# Audio.net
KiCad netlist of a schematic drawn in Altium Designer
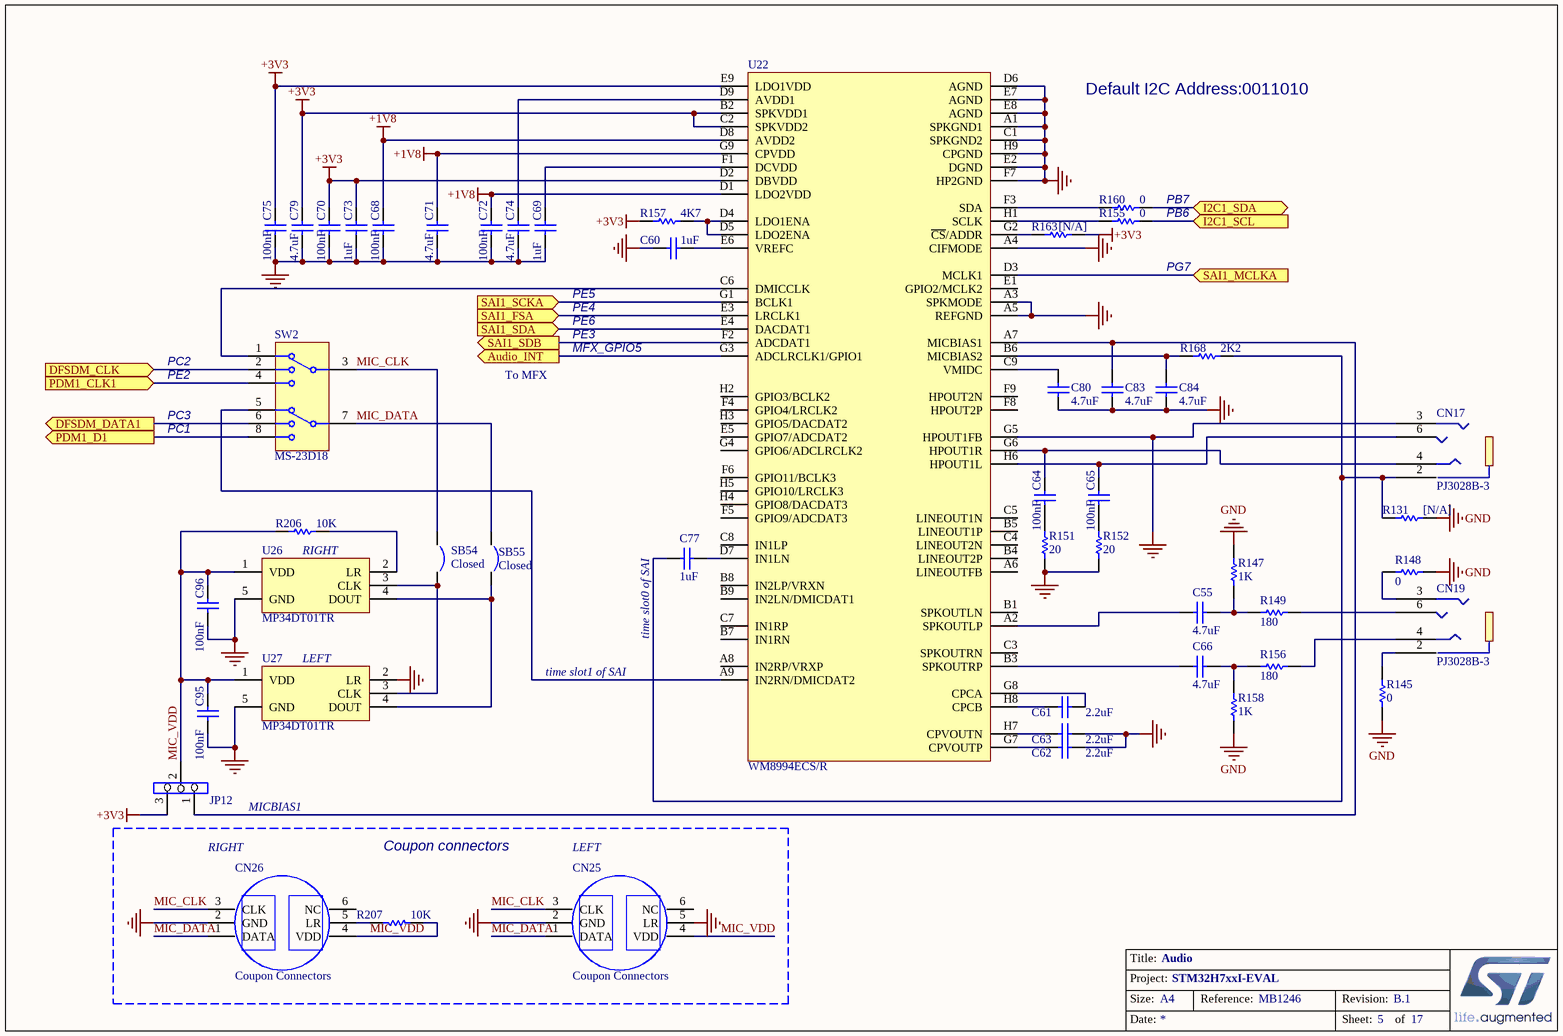
[diagram p0: Audio.SchDoc]

(export (version "E")
  (design (tool "Eeschema 10.0.6"))
  (components
    (comp (ref "C55")
      (value "4.7uF")
      (footprint "0603C")
      (description "Capacitor")
      (fields (field (name "PUBLISHER") "Altium Limited"))
      (libsource (lib "Miscellaneous Devices") (part "Cap"))
    )
    (comp (ref "C60")
      (value "1uF")
      (footprint "0603C")
      (description "Capacitor")
      (fields (field (name "PUBLISHER") "Altium Limited"))
      (libsource (lib "Miscellaneous Devices") (part "CAP"))
    )
    (comp (ref "C61")
      (value "2.2uF")
      (footprint "0603C")
      (description "Capacitor")
      (fields (field (name "PUBLISHER") "Altium Limited"))
      (libsource (lib "Miscellaneous Devices") (part "CAP"))
    )
    (comp (ref "C62")
      (value "2.2uF")
      (footprint "0603C")
      (description "Capacitor")
      (fields (field (name "PUBLISHER") "Altium Limited"))
      (libsource (lib "Miscellaneous Devices") (part "CAP"))
    )
    (comp (ref "C63")
      (value "2.2uF")
      (footprint "0603C")
      (description "Capacitor")
      (fields (field (name "PUBLISHER") "Altium Limited"))
      (libsource (lib "Miscellaneous Devices") (part "CAP"))
    )
    (comp (ref "C64")
      (value "100nF")
      (footprint "0603C")
      (description "Capacitor")
      (fields (field (name "PUBLISHER") "Altium Limited"))
      (libsource (lib "Miscellaneous Devices") (part "Cap"))
    )
    (comp (ref "C65")
      (value "100nF")
      (footprint "0603C")
      (description "Capacitor")
      (fields (field (name "PUBLISHER") "Altium Limited"))
      (libsource (lib "Miscellaneous Devices") (part "Cap"))
    )
    (comp (ref "C66")
      (value "4.7uF")
      (footprint "0603C")
      (description "Capacitor")
      (fields (field (name "PUBLISHER") "Altium Limited"))
      (libsource (lib "Miscellaneous Devices") (part "Cap"))
    )
    (comp (ref "C68")
      (value "100nF")
      (footprint "0603C")
      (description "Capacitor")
      (fields (field (name "PUBLISHER") "Altium Limited"))
      (libsource (lib "Miscellaneous Devices") (part "Cap"))
    )
    (comp (ref "C69")
      (value "1uF")
      (footprint "0603C")
      (description "Capacitor")
      (fields (field (name "PUBLISHER") "Altium Limited"))
      (libsource (lib "Miscellaneous Devices") (part "CAP"))
    )
    (comp (ref "C70")
      (value "100nF")
      (footprint "0603C")
      (description "Capacitor")
      (fields (field (name "PUBLISHER") "Altium Limited"))
      (libsource (lib "Miscellaneous Devices") (part "Cap"))
    )
    (comp (ref "C71")
      (value "4.7uF")
      (footprint "0603C")
      (description "Capacitor")
      (fields (field (name "PUBLISHER") "Altium Limited"))
      (libsource (lib "Miscellaneous Devices") (part "Cap"))
    )
    (comp (ref "C72")
      (value "100nF")
      (footprint "0603C")
      (description "Capacitor")
      (fields (field (name "PUBLISHER") "Altium Limited"))
      (libsource (lib "Miscellaneous Devices") (part "Cap"))
    )
    (comp (ref "C73")
      (value "1uF")
      (footprint "0603C")
      (description "Capacitor")
      (fields (field (name "PUBLISHER") "Altium Limited"))
      (libsource (lib "Miscellaneous Devices") (part "CAP"))
    )
    (comp (ref "C74")
      (value "4.7uF")
      (footprint "0603C")
      (description "Capacitor")
      (fields (field (name "PUBLISHER") "Altium Limited"))
      (libsource (lib "Miscellaneous Devices") (part "Cap"))
    )
    (comp (ref "C75")
      (value "100nF")
      (footprint "0603C")
      (description "Capacitor")
      (fields (field (name "PUBLISHER") "Altium Limited"))
      (libsource (lib "Miscellaneous Devices") (part "Cap"))
    )
    (comp (ref "C77")
      (value "1uF")
      (footprint "0603C")
      (description "Capacitor")
      (fields (field (name "PUBLISHER") "Altium Limited"))
      (libsource (lib "Miscellaneous Devices") (part "CAP"))
    )
    (comp (ref "C79")
      (value "4.7uF")
      (footprint "0603C")
      (description "Capacitor")
      (fields (field (name "PUBLISHER") "Altium Limited"))
      (libsource (lib "Miscellaneous Devices") (part "Cap"))
    )
    (comp (ref "C80")
      (value "4.7uF")
      (footprint "0603C")
      (description "Capacitor")
      (fields (field (name "PUBLISHER") "Altium Limited"))
      (libsource (lib "Miscellaneous Devices") (part "Cap"))
    )
    (comp (ref "C83")
      (value "4.7uF")
      (footprint "0603C")
      (description "Capacitor")
      (fields (field (name "PUBLISHER") "Altium Limited"))
      (libsource (lib "Miscellaneous Devices") (part "Cap"))
    )
    (comp (ref "C84")
      (value "4.7uF")
      (footprint "0603C")
      (description "Capacitor")
      (fields (field (name "PUBLISHER") "Altium Limited"))
      (libsource (lib "Miscellaneous Devices") (part "Cap"))
    )
    (comp (ref "C95")
      (value "100nF")
      (footprint "0603C")
      (description "Capacitor")
      (fields (field (name "PUBLISHER") "Altium Limited"))
      (libsource (lib "Miscellaneous Devices") (part "Cap"))
    )
    (comp (ref "C96")
      (value "100nF")
      (footprint "0603C")
      (description "Capacitor")
      (fields (field (name "PUBLISHER") "Altium Limited"))
      (libsource (lib "Miscellaneous Devices") (part "Cap"))
    )
    (comp (ref "CN17") (value "PJ3028B-3") (footprint "PJ3028B") (libsource (lib "MB786") (part "PJ3028B-3")))
    (comp (ref "CN19") (value "PJ3028B-3") (footprint "PJ3028B") (libsource (lib "MB786") (part "PJ3028B-3")))
    (comp (ref "CN25")
      (value "Coupon Connectors")
      (footprint "Coupon")
      (description "Header, 3-Pin, Single row")
      (fields (field (name "PUBLISHER") "Altium Limited"))
      (libsource (lib "MB1167") (part "Coupon Connectors"))
    )
    (comp (ref "CN26")
      (value "Coupon Connectors")
      (footprint "Coupon")
      (description "Header, 3-Pin, Single row")
      (fields (field (name "PUBLISHER") "Altium Limited"))
      (libsource (lib "MB1167") (part "Coupon Connectors"))
    )
    (comp (ref "JP12") (value "~") (footprint "SIP3") (libsource (lib "STR910_SCHLIB") (part "Jumper3")))
    (comp (ref "R131")
      (value "[N/A]")
      (footprint "0603R")
      (description "Resistor")
      (fields (field (name "PUBLISHER") "Altium Limited"))
      (libsource (lib "Miscellaneous Devices") (part "Res1"))
    )
    (comp (ref "R145")
      (value "0")
      (footprint "0603R")
      (description "Resistor")
      (fields (field (name "PUBLISHER") "Altium Limited"))
      (libsource (lib "Miscellaneous Devices") (part "Res1"))
    )
    (comp (ref "R147")
      (value "1K")
      (footprint "0402R")
      (description "Resistor")
      (fields (field (name "PUBLISHER") "Altium Limited"))
      (libsource (lib "Miscellaneous Devices") (part "Res1"))
    )
    (comp (ref "R148")
      (value "0")
      (footprint "0603R")
      (description "Resistor")
      (fields (field (name "PUBLISHER") "Altium Limited"))
      (libsource (lib "Miscellaneous Devices") (part "Res1"))
    )
    (comp (ref "R149")
      (value "180")
      (footprint "0402R")
      (description "Resistor")
      (fields (field (name "PUBLISHER") "Altium Limited"))
      (libsource (lib "Miscellaneous Devices") (part "Res1"))
    )
    (comp (ref "R151")
      (value "20")
      (footprint "0603R")
      (description "Resistor")
      (fields (field (name "PUBLISHER") "Altium Limited"))
      (libsource (lib "Miscellaneous Devices") (part "Res1"))
    )
    (comp (ref "R152")
      (value "20")
      (footprint "0603R")
      (description "Resistor")
      (fields (field (name "PUBLISHER") "Altium Limited"))
      (libsource (lib "Miscellaneous Devices") (part "Res1"))
    )
    (comp (ref "R155")
      (value "0")
      (footprint "0603R")
      (description "Resistor")
      (fields (field (name "PUBLISHER") "Altium Limited"))
      (libsource (lib "Miscellaneous Devices") (part "Res1"))
    )
    (comp (ref "R156")
      (value "180")
      (footprint "0402R")
      (description "Resistor")
      (fields (field (name "PUBLISHER") "Altium Limited"))
      (libsource (lib "Miscellaneous Devices") (part "Res1"))
    )
    (comp (ref "R157")
      (value "4K7")
      (footprint "0603R")
      (description "Resistor")
      (fields (field (name "PUBLISHER") "Altium Limited"))
      (libsource (lib "Miscellaneous Devices") (part "Res1"))
    )
    (comp (ref "R158")
      (value "1K")
      (footprint "0402R")
      (description "Resistor")
      (fields (field (name "PUBLISHER") "Altium Limited"))
      (libsource (lib "Miscellaneous Devices") (part "Res1"))
    )
    (comp (ref "R160")
      (value "0")
      (footprint "0603R")
      (description "Resistor")
      (fields (field (name "PUBLISHER") "Altium Limited"))
      (libsource (lib "Miscellaneous Devices") (part "Res1"))
    )
    (comp (ref "R163")
      (value "[N/A]")
      (footprint "0603R")
      (description "Resistor")
      (fields (field (name "PUBLISHER") "Altium Limited"))
      (libsource (lib "Miscellaneous Devices") (part "Res1"))
    )
    (comp (ref "R168")
      (value "2K2")
      (footprint "0603R")
      (description "Resistor")
      (fields (field (name "PUBLISHER") "Altium Limited"))
      (libsource (lib "Miscellaneous Devices") (part "Res1"))
    )
    (comp (ref "R206")
      (value "10K")
      (footprint "0603R")
      (description "Resistor")
      (fields (field (name "PUBLISHER") "Altium Limited"))
      (libsource (lib "Miscellaneous Devices") (part "Res1"))
    )
    (comp (ref "R207")
      (value "10K")
      (footprint "0603R")
      (description "Resistor")
      (fields (field (name "PUBLISHER") "Altium Limited"))
      (libsource (lib "Miscellaneous Devices") (part "Res1"))
    )
    (comp (ref "SB54")
      (value "Closed")
      (footprint "SB_0603")
      (description "Circuit Breaker")
      (fields (field (name "PUBLISHER") "Altium Limited"))
      (libsource (lib "MB1165") (part "Circuit Breaker_close"))
    )
    (comp (ref "SB55")
      (value "Closed")
      (footprint "SB_0603")
      (description "Circuit Breaker")
      (fields (field (name "PUBLISHER") "Altium Limited"))
      (libsource (lib "MB1165") (part "Circuit Breaker_close"))
    )
    (comp (ref "SW2")
      (value "MS-23D18")
      (footprint "SW1_8TH_13X3R5")
      (description "DPDT")
      (fields (field (name "PUBLISHER") "Altium Limited"))
      (libsource (lib "MB1246") (part "MS-23D18"))
    )
    (comp (ref "U22")
      (value "WM8994ECS/R")
      (footprint "BGA72_0R5_4R5X4")
      (libsource (lib "mb1045") (part "WM8994ECS/R"))
    )
    (comp (ref "U26")
      (value "MP34DT01TR")
      (footprint "MP34DT01TR")
      (description "MEMS audio sensor")
      (fields (field (name "PUBLISHER") "Altium Limited"))
      (libsource (lib "mb1045") (part "MP34DT01TR"))
    )
    (comp (ref "U27")
      (value "MP34DT01TR")
      (footprint "MP34DT01TR")
      (description "MEMS audio sensor")
      (fields (field (name "PUBLISHER") "Altium Limited"))
      (libsource (lib "mb1045") (part "MP34DT01TR"))
    )
  )
  (nets
    (net (code "1") (name "+1V8") (class "Default")
      (node (ref "C68") (pin "1") (pinfunction "1_1") (pintype "passive"))
      (node (ref "C71") (pin "1") (pinfunction "1_1") (pintype "passive"))
      (node (ref "C72") (pin "1") (pinfunction "1_1") (pintype "passive"))
      (node (ref "U22") (pin "D1") (pinfunction "LDO2VDD_D1") (pintype "passive"))
      (node (ref "U22") (pin "D8") (pinfunction "AVDD2_D8") (pintype "passive"))
      (node (ref "U22") (pin "G9") (pinfunction "CPVDD_G9") (pintype "passive"))
    )
    (net (code "2") (name "+3V3") (class "Default")
      (node (ref "C70") (pin "1") (pinfunction "1_1") (pintype "passive"))
      (node (ref "C73") (pin "1") (pinfunction "1_1") (pintype "passive"))
      (node (ref "C75") (pin "1") (pinfunction "1_1") (pintype "passive"))
      (node (ref "C79") (pin "1") (pinfunction "1_1") (pintype "passive"))
      (node (ref "JP12") (pin "3") (pintype "passive"))
      (node (ref "R157") (pin "2") (pinfunction "2_2") (pintype "passive"))
      (node (ref "R163") (pin "1") (pinfunction "1_1") (pintype "passive"))
      (node (ref "U22") (pin "B2") (pinfunction "SPKVDD1_B2") (pintype "passive"))
      (node (ref "U22") (pin "C2") (pinfunction "SPKVDD2_C2") (pintype "passive"))
      (node (ref "U22") (pin "D2") (pinfunction "DBVDD_D2") (pintype "passive"))
      (node (ref "U22") (pin "E9") (pinfunction "LDO1VDD_E9") (pintype "passive"))
    )
    (net (code "3") (name "/Audio_INT") (class "Default")
      (node (ref "U22") (pin "G3") (pinfunction "ADCLRCLK1/GPIO1_G3") (pintype "passive"))
    )
    (net (code "4") (name "/DFSDM_CLK") (class "Default") (node (ref "SW2") (pin "2") (pintype "passive")))
    (net (code "5") (name "/DFSDM_DATA1") (class "Default") (node (ref "SW2") (pin "6") (pintype "passive")))
    (net (code "6") (name "/I2C1_SCL") (class "Default")
      (node (ref "R155") (pin "1") (pinfunction "1_1") (pintype "passive"))
    )
    (net (code "7") (name "/I2C1_SDA") (class "Default")
      (node (ref "R160") (pin "1") (pinfunction "1_1") (pintype "passive"))
    )
    (net (code "8") (name "/MIC_CLK") (class "Default")
      (node (ref "CN25") (pin "3") (pinfunction "CLK_3") (pintype "passive"))
      (node (ref "CN26") (pin "3") (pinfunction "CLK_3") (pintype "passive"))
      (node (ref "SB54") (pin "1") (pinfunction "1_1") (pintype "passive"))
      (node (ref "SW2") (pin "3") (pintype "passive"))
    )
    (net (code "9") (name "/MIC_DATA") (class "Default")
      (node (ref "CN25") (pin "1") (pinfunction "DATA_1") (pintype "passive"))
      (node (ref "CN26") (pin "1") (pinfunction "DATA_1") (pintype "passive"))
      (node (ref "SB55") (pin "1") (pinfunction "1_1") (pintype "passive"))
      (node (ref "SW2") (pin "7") (pintype "passive"))
    )
    (net (code "10") (name "/MIC_VDD") (class "Default")
      (node (ref "C95") (pin "1") (pinfunction "1_1") (pintype "passive"))
      (node (ref "C96") (pin "1") (pinfunction "1_1") (pintype "passive"))
      (node (ref "CN25") (pin "4") (pinfunction "VDD_4") (pintype "passive"))
      (node (ref "CN26") (pin "4") (pinfunction "VDD_4") (pintype "passive"))
      (node (ref "JP12") (pin "2") (pintype "passive"))
      (node (ref "R206") (pin "2") (pinfunction "2_2") (pintype "passive"))
      (node (ref "R207") (pin "2") (pinfunction "2_2") (pintype "passive"))
      (node (ref "U26") (pin "1") (pinfunction "VDD_1") (pintype "passive"))
      (node (ref "U27") (pin "1") (pinfunction "VDD_1") (pintype "passive"))
    )
    (net (code "11") (name "/PDM1_CLK1") (class "Default") (node (ref "SW2") (pin "4") (pintype "passive")))
    (net (code "12") (name "/PDM1_D1") (class "Default") (node (ref "SW2") (pin "8") (pintype "passive")))
    (net (code "13") (name "/SAI1_FSA") (class "Default")
      (node (ref "U22") (pin "E3") (pinfunction "LRCLK1_E3") (pintype "passive"))
    )
    (net (code "14") (name "/SAI1_MCLKA") (class "Default")
      (node (ref "U22") (pin "D3") (pinfunction "MCLK1_D3") (pintype "passive"))
    )
    (net (code "15") (name "/SAI1_SCKA") (class "Default")
      (node (ref "U22") (pin "G1") (pinfunction "BCLK1_G1") (pintype "passive"))
    )
    (net (code "16") (name "/SAI1_SDA") (class "Default")
      (node (ref "U22") (pin "E4") (pinfunction "DACDAT1_E4") (pintype "passive"))
    )
    (net (code "17") (name "/SAI1_SDB") (class "Default")
      (node (ref "U22") (pin "F2") (pinfunction "ADCDAT1_F2") (pintype "passive"))
    )
    (net (code "18") (name "GND") (class "Default")
      (node (ref "C60") (pin "2") (pinfunction "2_2") (pintype "passive"))
      (node (ref "C62") (pin "2") (pinfunction "2_2") (pintype "passive"))
      (node (ref "C63") (pin "2") (pinfunction "2_2") (pintype "passive"))
      (node (ref "C68") (pin "2") (pinfunction "2_2") (pintype "passive"))
      (node (ref "C69") (pin "2") (pinfunction "2_2") (pintype "passive"))
      (node (ref "C70") (pin "2") (pinfunction "2_2") (pintype "passive"))
      (node (ref "C71") (pin "2") (pinfunction "2_2") (pintype "passive"))
      (node (ref "C72") (pin "2") (pinfunction "2_2") (pintype "passive"))
      (node (ref "C73") (pin "2") (pinfunction "2_2") (pintype "passive"))
      (node (ref "C74") (pin "2") (pinfunction "2_2") (pintype "passive"))
      (node (ref "C75") (pin "2") (pinfunction "2_2") (pintype "passive"))
      (node (ref "C79") (pin "2") (pinfunction "2_2") (pintype "passive"))
      (node (ref "C80") (pin "1") (pinfunction "1_1") (pintype "passive"))
      (node (ref "C83") (pin "1") (pinfunction "1_1") (pintype "passive"))
      (node (ref "C84") (pin "1") (pinfunction "1_1") (pintype "passive"))
      (node (ref "C95") (pin "2") (pinfunction "2_2") (pintype "passive"))
      (node (ref "C96") (pin "2") (pinfunction "2_2") (pintype "passive"))
      (node (ref "CN17") (pin "3") (pintype "passive"))
      (node (ref "CN25") (pin "2") (pinfunction "GND_2") (pintype "passive"))
      (node (ref "CN25") (pin "5") (pinfunction "LR_5") (pintype "passive"))
      (node (ref "CN26") (pin "2") (pinfunction "GND_2") (pintype "passive"))
      (node (ref "R131") (pin "1") (pinfunction "1_1") (pintype "passive"))
      (node (ref "R145") (pin "2") (pinfunction "2_2") (pintype "passive"))
      (node (ref "R147") (pin "2") (pinfunction "2_2") (pintype "passive"))
      (node (ref "R148") (pin "2") (pinfunction "2_2") (pintype "passive"))
      (node (ref "R151") (pin "2") (pinfunction "2_2") (pintype "passive"))
      (node (ref "R152") (pin "2") (pinfunction "2_2") (pintype "passive"))
      (node (ref "R158") (pin "1") (pinfunction "1_1") (pintype "passive"))
      (node (ref "U22") (pin "A1") (pinfunction "SPKGND1_A1") (pintype "passive"))
      (node (ref "U22") (pin "A3") (pinfunction "SPKMODE_A3") (pintype "passive"))
      (node (ref "U22") (pin "A4") (pinfunction "CIFMODE_A4") (pintype "passive"))
      (node (ref "U22") (pin "A5") (pinfunction "REFGND_A5") (pintype "passive"))
      (node (ref "U22") (pin "C1") (pinfunction "SPKGND2_C1") (pintype "passive"))
      (node (ref "U22") (pin "D6") (pinfunction "AGND_D6") (pintype "passive"))
      (node (ref "U22") (pin "E2") (pinfunction "DGND_E2") (pintype "passive"))
      (node (ref "U22") (pin "E7") (pinfunction "AGND_E7") (pintype "passive"))
      (node (ref "U22") (pin "E8") (pinfunction "AGND_E8") (pintype "passive"))
      (node (ref "U22") (pin "F7") (pinfunction "HP2GND_F7") (pintype "passive"))
      (node (ref "U22") (pin "G5") (pinfunction "HPOUT1FB_G5") (pintype "passive"))
      (node (ref "U22") (pin "H9") (pinfunction "CPGND_H9") (pintype "passive"))
      (node (ref "U26") (pin "5") (pinfunction "GND_5") (pintype "passive"))
      (node (ref "U27") (pin "2") (pinfunction "LR_2") (pintype "passive"))
      (node (ref "U27") (pin "5") (pinfunction "GND_5") (pintype "passive"))
    )
    (net (code "19") (name "Net-(C55-Pad1)") (class "Default")
      (node (ref "C55") (pin "1") (pinfunction "1_1") (pintype "passive"))
      (node (ref "R147") (pin "1") (pinfunction "1_1") (pintype "passive"))
      (node (ref "R149") (pin "1") (pinfunction "1_1") (pintype "passive"))
    )
    (net (code "20") (name "Net-(C64-Pad2)") (class "Default")
      (node (ref "C64") (pin "2") (pinfunction "2_2") (pintype "passive"))
      (node (ref "R151") (pin "1") (pinfunction "1_1") (pintype "passive"))
    )
    (net (code "21") (name "Net-(C65-Pad2)") (class "Default")
      (node (ref "C65") (pin "2") (pinfunction "2_2") (pintype "passive"))
      (node (ref "R152") (pin "1") (pinfunction "1_1") (pintype "passive"))
    )
    (net (code "22") (name "Net-(C66-Pad1)") (class "Default")
      (node (ref "C66") (pin "1") (pinfunction "1_1") (pintype "passive"))
      (node (ref "R156") (pin "2") (pinfunction "2_2") (pintype "passive"))
      (node (ref "R158") (pin "2") (pinfunction "2_2") (pintype "passive"))
    )
    (net (code "23") (name "Net-(C77-Pad2)") (class "Default")
      (node (ref "C77") (pin "2") (pinfunction "2_2") (pintype "passive"))
      (node (ref "CN17") (pin "2") (pintype "passive"))
      (node (ref "R131") (pin "2") (pinfunction "2_2") (pintype "passive"))
      (node (ref "R168") (pin "1") (pinfunction "1_1") (pintype "passive"))
    )
    (net (code "24") (name "Net-(CN19-Pad2)") (class "Default")
      (node (ref "CN19") (pin "2") (pintype "passive"))
      (node (ref "R145") (pin "1") (pinfunction "1_1") (pintype "passive"))
    )
    (net (code "25") (name "Net-(CN19-Pad3)") (class "Default")
      (node (ref "CN19") (pin "3") (pintype "passive"))
      (node (ref "R148") (pin "1") (pinfunction "1_1") (pintype "passive"))
    )
    (net (code "26") (name "Net-(CN19-Pad4)") (class "Default")
      (node (ref "CN19") (pin "4") (pintype "passive"))
      (node (ref "R156") (pin "1") (pinfunction "1_1") (pintype "passive"))
    )
    (net (code "27") (name "Net-(CN19-Pad6)") (class "Default")
      (node (ref "CN19") (pin "6") (pintype "passive"))
      (node (ref "R149") (pin "2") (pinfunction "2_2") (pintype "passive"))
    )
    (net (code "28") (name "Net-(CN26-LR)") (class "Default")
      (node (ref "CN26") (pin "5") (pinfunction "LR_5") (pintype "passive"))
      (node (ref "R207") (pin "1") (pinfunction "1_1") (pintype "passive"))
    )
    (net (code "29") (name "Net-(U22-AVDD1)") (class "Default")
      (node (ref "C74") (pin "1") (pinfunction "1_1") (pintype "passive"))
      (node (ref "U22") (pin "D9") (pinfunction "AVDD1_D9") (pintype "passive"))
    )
    (net (code "30") (name "Net-(U22-CPCA)") (class "Default")
      (node (ref "C61") (pin "2") (pinfunction "2_2") (pintype "passive"))
      (node (ref "U22") (pin "G8") (pinfunction "CPCA_G8") (pintype "passive"))
    )
    (net (code "31") (name "Net-(U22-CPCB)") (class "Default")
      (node (ref "C61") (pin "1") (pinfunction "1_1") (pintype "passive"))
      (node (ref "U22") (pin "H8") (pinfunction "CPCB_H8") (pintype "passive"))
    )
    (net (code "32") (name "Net-(U22-CPVOUTN)") (class "Default")
      (node (ref "C63") (pin "1") (pinfunction "1_1") (pintype "passive"))
      (node (ref "U22") (pin "H7") (pinfunction "CPVOUTN_H7") (pintype "passive"))
    )
    (net (code "33") (name "Net-(U22-CPVOUTP)") (class "Default")
      (node (ref "C62") (pin "1") (pinfunction "1_1") (pintype "passive"))
      (node (ref "U22") (pin "G7") (pinfunction "CPVOUTP_G7") (pintype "passive"))
    )
    (net (code "34") (name "Net-(U22-DCVDD)") (class "Default")
      (node (ref "C69") (pin "1") (pinfunction "1_1") (pintype "passive"))
      (node (ref "U22") (pin "F1") (pinfunction "DCVDD_F1") (pintype "passive"))
    )
    (net (code "35") (name "Net-(U22-DMICCLK)") (class "Default")
      (node (ref "SW2") (pin "1") (pintype "passive"))
      (node (ref "U22") (pin "C6") (pinfunction "DMICCLK_C6") (pintype "passive"))
    )
    (net (code "36") (name "Net-(U22-HPOUT1L)") (class "Default")
      (node (ref "C65") (pin "1") (pinfunction "1_1") (pintype "passive"))
      (node (ref "CN17") (pin "6") (pintype "passive"))
      (node (ref "U22") (pin "H6") (pinfunction "HPOUT1L_H6") (pintype "passive"))
    )
    (net (code "37") (name "Net-(U22-HPOUT1R)") (class "Default")
      (node (ref "C64") (pin "1") (pinfunction "1_1") (pintype "passive"))
      (node (ref "CN17") (pin "4") (pintype "passive"))
      (node (ref "U22") (pin "G6") (pinfunction "HPOUT1R_G6") (pintype "passive"))
    )
    (net (code "38") (name "Net-(U22-IN1LN)") (class "Default")
      (node (ref "C77") (pin "1") (pinfunction "1_1") (pintype "passive"))
      (node (ref "U22") (pin "D7") (pinfunction "IN1LN_D7") (pintype "passive"))
    )
    (net (code "39") (name "Net-(U22-IN2RN{slash}DMICDAT2)") (class "Default")
      (node (ref "SW2") (pin "5") (pintype "passive"))
      (node (ref "U22") (pin "A9") (pinfunction "IN2RN/DMICDAT2_A9") (pintype "passive"))
    )
    (net (code "40") (name "Net-(U22-LDO1ENA)") (class "Default")
      (node (ref "R157") (pin "1") (pinfunction "1_1") (pintype "passive"))
      (node (ref "U22") (pin "D4") (pinfunction "LDO1ENA_D4") (pintype "passive"))
      (node (ref "U22") (pin "D5") (pinfunction "LDO2ENA_D5") (pintype "passive"))
    )
    (net (code "41") (name "Net-(U22-MICBIAS1)") (class "Default")
      (node (ref "C83") (pin "2") (pinfunction "2_2") (pintype "passive"))
      (node (ref "JP12") (pin "1") (pintype "passive"))
      (node (ref "U22") (pin "A7") (pinfunction "MICBIAS1_A7") (pintype "passive"))
    )
    (net (code "42") (name "Net-(U22-MICBIAS2)") (class "Default")
      (node (ref "C84") (pin "2") (pinfunction "2_2") (pintype "passive"))
      (node (ref "R168") (pin "2") (pinfunction "2_2") (pintype "passive"))
      (node (ref "U22") (pin "B6") (pinfunction "MICBIAS2_B6") (pintype "passive"))
    )
    (net (code "43") (name "Net-(U22-SCLK)") (class "Default")
      (node (ref "R155") (pin "2") (pinfunction "2_2") (pintype "passive"))
      (node (ref "U22") (pin "H1") (pinfunction "SCLK_H1") (pintype "passive"))
    )
    (net (code "44") (name "Net-(U22-SDA)") (class "Default")
      (node (ref "R160") (pin "2") (pinfunction "2_2") (pintype "passive"))
      (node (ref "U22") (pin "F3") (pinfunction "SDA_F3") (pintype "passive"))
    )
    (net (code "45") (name "Net-(U22-SPKOUTLP)") (class "Default")
      (node (ref "C55") (pin "2") (pinfunction "2_2") (pintype "passive"))
      (node (ref "U22") (pin "A2") (pinfunction "SPKOUTLP_A2") (pintype "passive"))
    )
    (net (code "46") (name "Net-(U22-SPKOUTRP)") (class "Default")
      (node (ref "C66") (pin "2") (pinfunction "2_2") (pintype "passive"))
      (node (ref "U22") (pin "B3") (pinfunction "SPKOUTRP_B3") (pintype "passive"))
    )
    (net (code "47") (name "Net-(U22-VMIDC)") (class "Default")
      (node (ref "C80") (pin "2") (pinfunction "2_2") (pintype "passive"))
      (node (ref "U22") (pin "C9") (pinfunction "VMIDC_C9") (pintype "passive"))
    )
    (net (code "48") (name "Net-(U22-VREFC)") (class "Default")
      (node (ref "C60") (pin "1") (pinfunction "1_1") (pintype "passive"))
      (node (ref "U22") (pin "E6") (pinfunction "VREFC_E6") (pintype "passive"))
    )
    (net (code "49") (name "Net-(U22-~{CS}{slash}ADDR)") (class "Default")
      (node (ref "R163") (pin "2") (pinfunction "2_2") (pintype "passive"))
      (node (ref "U22") (pin "G2") (pinfunction "~{CS}/ADDR_G2") (pintype "passive"))
    )
    (net (code "50") (name "Net-(U26-CLK)") (class "Default")
      (node (ref "SB54") (pin "2") (pinfunction "2_2") (pintype "passive"))
      (node (ref "U26") (pin "3") (pinfunction "CLK_3") (pintype "passive"))
      (node (ref "U27") (pin "3") (pinfunction "CLK_3") (pintype "passive"))
    )
    (net (code "51") (name "Net-(U26-DOUT)") (class "Default")
      (node (ref "SB55") (pin "2") (pinfunction "2_2") (pintype "passive"))
      (node (ref "U26") (pin "4") (pinfunction "DOUT_4") (pintype "passive"))
      (node (ref "U27") (pin "4") (pinfunction "DOUT_4") (pintype "passive"))
    )
    (net (code "52") (name "Net-(U26-LR)") (class "Default")
      (node (ref "R206") (pin "1") (pinfunction "1_1") (pintype "passive"))
      (node (ref "U26") (pin "2") (pinfunction "LR_2") (pintype "passive"))
    )
    (net (code "53") (name "unconnected-(CN25-NC-Pad6)") (class "Default")
      (node (ref "CN25") (pin "6") (pinfunction "NC_6") (pintype "passive"))
    )
    (net (code "54") (name "unconnected-(CN26-NC-Pad6)") (class "Default")
      (node (ref "CN26") (pin "6") (pinfunction "NC_6") (pintype "passive"))
    )
    (net (code "55") (name "unconnected-(U22-GPIO2{slash}MCLK2-PadE1)") (class "Default")
      (node (ref "U22") (pin "E1") (pinfunction "GPIO2/MCLK2_E1") (pintype "passive"))
    )
    (net (code "56") (name "unconnected-(U22-GPIO3{slash}BCLK2-PadH2)") (class "Default")
      (node (ref "U22") (pin "H2") (pinfunction "GPIO3/BCLK2_H2") (pintype "passive"))
    )
    (net (code "57") (name "unconnected-(U22-GPIO4{slash}LRCLK2-PadF4)") (class "Default")
      (node (ref "U22") (pin "F4") (pinfunction "GPIO4/LRCLK2_F4") (pintype "passive"))
    )
    (net (code "58") (name "unconnected-(U22-GPIO5{slash}DACDAT2-PadH3)") (class "Default")
      (node (ref "U22") (pin "H3") (pinfunction "GPIO5/DACDAT2_H3") (pintype "passive"))
    )
    (net (code "59") (name "unconnected-(U22-GPIO6{slash}ADCLRCLK2-PadG4)") (class "Default")
      (node (ref "U22") (pin "G4") (pinfunction "GPIO6/ADCLRCLK2_G4") (pintype "passive"))
    )
    (net (code "60") (name "unconnected-(U22-GPIO7{slash}ADCDAT2-PadE5)") (class "Default")
      (node (ref "U22") (pin "E5") (pinfunction "GPIO7/ADCDAT2_E5") (pintype "passive"))
    )
    (net (code "61") (name "unconnected-(U22-GPIO8{slash}DACDAT3-PadH4)") (class "Default")
      (node (ref "U22") (pin "H4") (pinfunction "GPIO8/DACDAT3_H4") (pintype "passive"))
    )
    (net (code "62") (name "unconnected-(U22-GPIO9{slash}ADCDAT3-PadF5)") (class "Default")
      (node (ref "U22") (pin "F5") (pinfunction "GPIO9/ADCDAT3_F5") (pintype "passive"))
    )
    (net (code "63") (name "unconnected-(U22-GPIO10{slash}LRCLK3-PadH5)") (class "Default")
      (node (ref "U22") (pin "H5") (pinfunction "GPIO10/LRCLK3_H5") (pintype "passive"))
    )
    (net (code "64") (name "unconnected-(U22-GPIO11{slash}BCLK3-PadF6)") (class "Default")
      (node (ref "U22") (pin "F6") (pinfunction "GPIO11/BCLK3_F6") (pintype "passive"))
    )
    (net (code "65") (name "unconnected-(U22-HPOUT2N-PadF9)") (class "Default")
      (node (ref "U22") (pin "F9") (pinfunction "HPOUT2N_F9") (pintype "passive"))
    )
    (net (code "66") (name "unconnected-(U22-HPOUT2P-PadF8)") (class "Default")
      (node (ref "U22") (pin "F8") (pinfunction "HPOUT2P_F8") (pintype "passive"))
    )
    (net (code "67") (name "unconnected-(U22-IN1LP-PadC8)") (class "Default")
      (node (ref "U22") (pin "C8") (pinfunction "IN1LP_C8") (pintype "passive"))
    )
    (net (code "68") (name "unconnected-(U22-IN1RN-PadB7)") (class "Default")
      (node (ref "U22") (pin "B7") (pinfunction "IN1RN_B7") (pintype "passive"))
    )
    (net (code "69") (name "unconnected-(U22-IN1RP-PadC7)") (class "Default")
      (node (ref "U22") (pin "C7") (pinfunction "IN1RP_C7") (pintype "passive"))
    )
    (net (code "70") (name "unconnected-(U22-IN2LN{slash}DMICDAT1-PadB9)") (class "Default")
      (node (ref "U22") (pin "B9") (pinfunction "IN2LN/DMICDAT1_B9") (pintype "passive"))
    )
    (net (code "71") (name "unconnected-(U22-IN2LP{slash}VRXN-PadB8)") (class "Default")
      (node (ref "U22") (pin "B8") (pinfunction "IN2LP/VRXN_B8") (pintype "passive"))
    )
    (net (code "72") (name "unconnected-(U22-IN2RP{slash}VRXP-PadA8)") (class "Default")
      (node (ref "U22") (pin "A8") (pinfunction "IN2RP/VRXP_A8") (pintype "passive"))
    )
    (net (code "73") (name "unconnected-(U22-LINEOUT1N-PadC5)") (class "Default")
      (node (ref "U22") (pin "C5") (pinfunction "LINEOUT1N_C5") (pintype "passive"))
    )
    (net (code "74") (name "unconnected-(U22-LINEOUT1P-PadB5)") (class "Default")
      (node (ref "U22") (pin "B5") (pinfunction "LINEOUT1P_B5") (pintype "passive"))
    )
    (net (code "75") (name "unconnected-(U22-LINEOUT2N-PadC4)") (class "Default")
      (node (ref "U22") (pin "C4") (pinfunction "LINEOUT2N_C4") (pintype "passive"))
    )
    (net (code "76") (name "unconnected-(U22-LINEOUT2P-PadB4)") (class "Default")
      (node (ref "U22") (pin "B4") (pinfunction "LINEOUT2P_B4") (pintype "passive"))
    )
    (net (code "77") (name "unconnected-(U22-LINEOUTFB-PadA6)") (class "Default")
      (node (ref "U22") (pin "A6") (pinfunction "LINEOUTFB_A6") (pintype "passive"))
    )
    (net (code "78") (name "unconnected-(U22-SPKOUTLN-PadB1)") (class "Default")
      (node (ref "U22") (pin "B1") (pinfunction "SPKOUTLN_B1") (pintype "passive"))
    )
    (net (code "79") (name "unconnected-(U22-SPKOUTRN-PadC3)") (class "Default")
      (node (ref "U22") (pin "C3") (pinfunction "SPKOUTRN_C3") (pintype "passive"))
    )
  )
)
